# module_4dig7seg.net
KiCad netlist of a schematic drawn in EAGLE
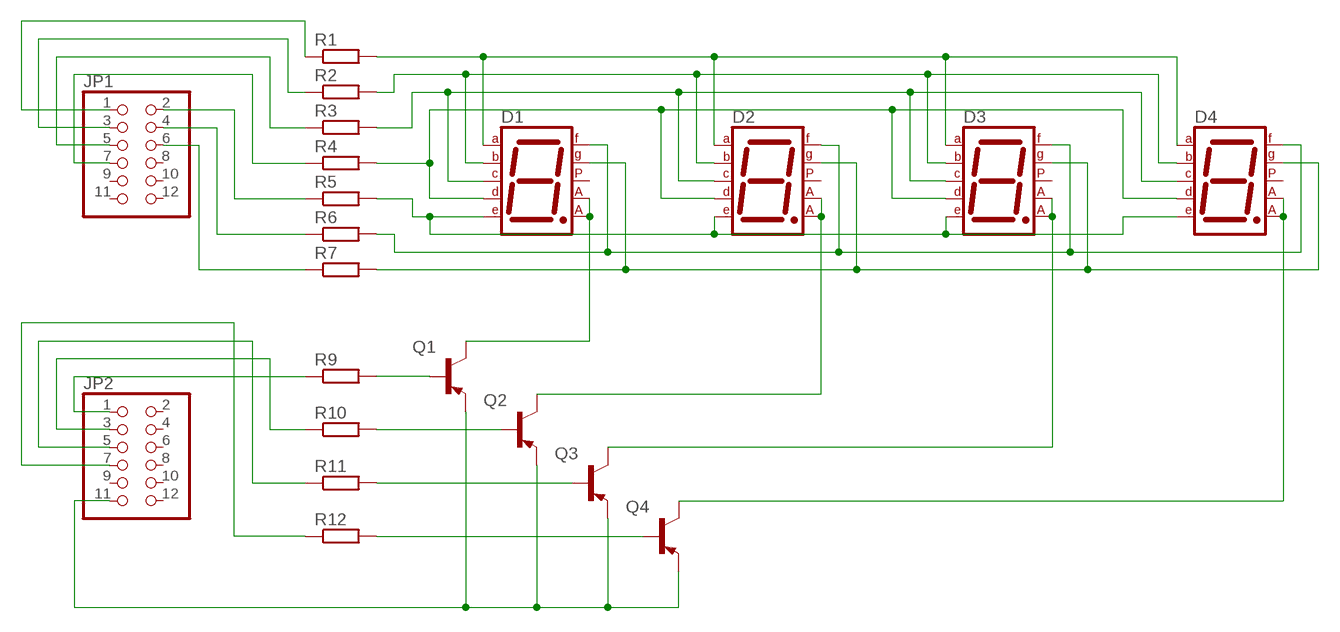
[diagram p0: schematic, sheet 1]

(export (version "E")
  (design (tool "Eeschema 10.0.6"))
  (components
    (comp (ref "D1")
      (value "7SEG-CA")
      (footprint "eagle-import:7SEG-13")
      (libsource (lib "eagle-import") (part "7SEG-CA"))
    )
    (comp (ref "D2")
      (value "7SEG-CA")
      (footprint "eagle-import:7SEG-13")
      (libsource (lib "eagle-import") (part "7SEG-CA"))
    )
    (comp (ref "D3")
      (value "7SEG-CA")
      (footprint "eagle-import:7SEG-13")
      (libsource (lib "eagle-import") (part "7SEG-CA"))
    )
    (comp (ref "D4")
      (value "7SEG-CA")
      (footprint "eagle-import:7SEG-13")
      (libsource (lib "eagle-import") (part "7SEG-CA"))
    )
    (comp (ref "JP1")
      (value "PINHD-2X6/90")
      (footprint "eagle-import:2X06_90")
      (libsource (lib "eagle-import") (part "PINHD-2X6/90"))
    )
    (comp (ref "JP2")
      (value "PINHD-2X6/90")
      (footprint "eagle-import:2X06_90")
      (libsource (lib "eagle-import") (part "PINHD-2X6/90"))
    )
    (comp (ref "Q1")
      (value "2N3906")
      (footprint "eagle-import:TO92")
      (libsource (lib "eagle-import") (part "2N3906"))
    )
    (comp (ref "Q2")
      (value "2N3906")
      (footprint "eagle-import:TO92")
      (libsource (lib "eagle-import") (part "2N3906"))
    )
    (comp (ref "Q3")
      (value "2N3906")
      (footprint "eagle-import:TO92")
      (libsource (lib "eagle-import") (part "2N3906"))
    )
    (comp (ref "Q4")
      (value "2N3906")
      (footprint "eagle-import:TO92")
      (libsource (lib "eagle-import") (part "2N3906"))
    )
    (comp (ref "R1")
      (value "R-EU_0204/7")
      (footprint "eagle-import:0204_7")
      (libsource (lib "eagle-import") (part "R-EU_0204/7"))
    )
    (comp (ref "R2")
      (value "R-EU_0204/7")
      (footprint "eagle-import:0204_7")
      (libsource (lib "eagle-import") (part "R-EU_0204/7"))
    )
    (comp (ref "R3")
      (value "R-EU_0204/7")
      (footprint "eagle-import:0204_7")
      (libsource (lib "eagle-import") (part "R-EU_0204/7"))
    )
    (comp (ref "R4")
      (value "R-EU_0204/7")
      (footprint "eagle-import:0204_7")
      (libsource (lib "eagle-import") (part "R-EU_0204/7"))
    )
    (comp (ref "R5")
      (value "R-EU_0204/7")
      (footprint "eagle-import:0204_7")
      (libsource (lib "eagle-import") (part "R-EU_0204/7"))
    )
    (comp (ref "R6")
      (value "R-EU_0204/7")
      (footprint "eagle-import:0204_7")
      (libsource (lib "eagle-import") (part "R-EU_0204/7"))
    )
    (comp (ref "R7")
      (value "R-EU_0204/7")
      (footprint "eagle-import:0204_7")
      (libsource (lib "eagle-import") (part "R-EU_0204/7"))
    )
    (comp (ref "R9")
      (value "R-EU_0204/7")
      (footprint "eagle-import:0204_7")
      (libsource (lib "eagle-import") (part "R-EU_0204/7"))
    )
    (comp (ref "R10")
      (value "R-EU_0204/7")
      (footprint "eagle-import:0204_7")
      (libsource (lib "eagle-import") (part "R-EU_0204/7"))
    )
    (comp (ref "R11")
      (value "R-EU_0204/7")
      (footprint "eagle-import:0204_7")
      (libsource (lib "eagle-import") (part "R-EU_0204/7"))
    )
    (comp (ref "R12")
      (value "R-EU_0204/7")
      (footprint "eagle-import:0204_7")
      (libsource (lib "eagle-import") (part "R-EU_0204/7"))
    )
  )
  (nets
    (net (code "1") (name "Net-(D1-A)") (class "Default")
      (node (ref "D1") (pin "7") (pinfunction "A_7") (pintype "passive"))
      (node (ref "D2") (pin "7") (pinfunction "A_7") (pintype "passive"))
      (node (ref "D3") (pin "7") (pinfunction "A_7") (pintype "passive"))
      (node (ref "D4") (pin "7") (pinfunction "A_7") (pintype "passive"))
      (node (ref "R1") (pin "2") (pinfunction "2_2") (pintype "passive"))
    )
    (net (code "2") (name "Net-(D1-B)") (class "Default")
      (node (ref "D1") (pin "6") (pinfunction "B_6") (pintype "passive"))
      (node (ref "D2") (pin "6") (pinfunction "B_6") (pintype "passive"))
      (node (ref "D3") (pin "6") (pinfunction "B_6") (pintype "passive"))
      (node (ref "D4") (pin "6") (pinfunction "B_6") (pintype "passive"))
      (node (ref "R2") (pin "2") (pinfunction "2_2") (pintype "passive"))
    )
    (net (code "3") (name "Net-(D1-C)") (class "Default")
      (node (ref "D1") (pin "4") (pinfunction "C_4") (pintype "passive"))
      (node (ref "D2") (pin "4") (pinfunction "C_4") (pintype "passive"))
      (node (ref "D3") (pin "4") (pinfunction "C_4") (pintype "passive"))
      (node (ref "D4") (pin "4") (pinfunction "C_4") (pintype "passive"))
      (node (ref "R3") (pin "2") (pinfunction "2_2") (pintype "passive"))
    )
    (net (code "4") (name "Net-(D1-CA1)") (class "Default")
      (node (ref "D1") (pin "3") (pinfunction "CA1_3") (pintype "passive"))
      (node (ref "D1") (pin "8") (pinfunction "CA2_8") (pintype "passive"))
      (node (ref "Q1") (pin "1") (pinfunction "C_1") (pintype "passive"))
    )
    (net (code "5") (name "Net-(D1-D)") (class "Default")
      (node (ref "D1") (pin "2") (pinfunction "D_2") (pintype "passive"))
      (node (ref "D2") (pin "2") (pinfunction "D_2") (pintype "passive"))
      (node (ref "D3") (pin "2") (pinfunction "D_2") (pintype "passive"))
      (node (ref "D4") (pin "2") (pinfunction "D_2") (pintype "passive"))
      (node (ref "R4") (pin "2") (pinfunction "2_2") (pintype "passive"))
    )
    (net (code "6") (name "Net-(D1-E)") (class "Default")
      (node (ref "D1") (pin "1") (pinfunction "E_1") (pintype "passive"))
      (node (ref "D2") (pin "1") (pinfunction "E_1") (pintype "passive"))
      (node (ref "D3") (pin "1") (pinfunction "E_1") (pintype "passive"))
      (node (ref "D4") (pin "1") (pinfunction "E_1") (pintype "passive"))
      (node (ref "R5") (pin "2") (pinfunction "2_2") (pintype "passive"))
    )
    (net (code "7") (name "Net-(D1-F)") (class "Default")
      (node (ref "D1") (pin "9") (pinfunction "F_9") (pintype "passive"))
      (node (ref "D2") (pin "9") (pinfunction "F_9") (pintype "passive"))
      (node (ref "D3") (pin "9") (pinfunction "F_9") (pintype "passive"))
      (node (ref "D4") (pin "9") (pinfunction "F_9") (pintype "passive"))
      (node (ref "R6") (pin "2") (pinfunction "2_2") (pintype "passive"))
    )
    (net (code "8") (name "Net-(D1-G)") (class "Default")
      (node (ref "D1") (pin "10") (pinfunction "G_10") (pintype "passive"))
      (node (ref "D2") (pin "10") (pinfunction "G_10") (pintype "passive"))
      (node (ref "D3") (pin "10") (pinfunction "G_10") (pintype "passive"))
      (node (ref "D4") (pin "10") (pinfunction "G_10") (pintype "passive"))
      (node (ref "R7") (pin "2") (pinfunction "2_2") (pintype "passive"))
    )
    (net (code "9") (name "Net-(D2-CA1)") (class "Default")
      (node (ref "D2") (pin "3") (pinfunction "CA1_3") (pintype "passive"))
      (node (ref "D2") (pin "8") (pinfunction "CA2_8") (pintype "passive"))
      (node (ref "Q2") (pin "1") (pinfunction "C_1") (pintype "passive"))
    )
    (net (code "10") (name "Net-(D3-CA1)") (class "Default")
      (node (ref "D3") (pin "3") (pinfunction "CA1_3") (pintype "passive"))
      (node (ref "D3") (pin "8") (pinfunction "CA2_8") (pintype "passive"))
      (node (ref "Q3") (pin "1") (pinfunction "C_1") (pintype "passive"))
    )
    (net (code "11") (name "Net-(D4-CA1)") (class "Default")
      (node (ref "D4") (pin "3") (pinfunction "CA1_3") (pintype "passive"))
      (node (ref "D4") (pin "8") (pinfunction "CA2_8") (pintype "passive"))
      (node (ref "Q4") (pin "1") (pinfunction "C_1") (pintype "passive"))
    )
    (net (code "12") (name "Net-(JP1-Pad1)") (class "Default")
      (node (ref "JP1") (pin "1") (pinfunction "1_1") (pintype "passive"))
      (node (ref "R1") (pin "1") (pinfunction "1_1") (pintype "passive"))
    )
    (net (code "13") (name "Net-(JP1-Pad2)") (class "Default")
      (node (ref "JP1") (pin "2") (pinfunction "2_2") (pintype "passive"))
      (node (ref "R5") (pin "1") (pinfunction "1_1") (pintype "passive"))
    )
    (net (code "14") (name "Net-(JP1-Pad3)") (class "Default")
      (node (ref "JP1") (pin "3") (pinfunction "3_3") (pintype "passive"))
      (node (ref "R2") (pin "1") (pinfunction "1_1") (pintype "passive"))
    )
    (net (code "15") (name "Net-(JP1-Pad4)") (class "Default")
      (node (ref "JP1") (pin "4") (pinfunction "4_4") (pintype "passive"))
      (node (ref "R6") (pin "1") (pinfunction "1_1") (pintype "passive"))
    )
    (net (code "16") (name "Net-(JP1-Pad5)") (class "Default")
      (node (ref "JP1") (pin "5") (pinfunction "5_5") (pintype "passive"))
      (node (ref "R3") (pin "1") (pinfunction "1_1") (pintype "passive"))
    )
    (net (code "17") (name "Net-(JP1-Pad6)") (class "Default")
      (node (ref "JP1") (pin "6") (pinfunction "6_6") (pintype "passive"))
      (node (ref "R7") (pin "1") (pinfunction "1_1") (pintype "passive"))
    )
    (net (code "18") (name "Net-(JP1-Pad7)") (class "Default")
      (node (ref "JP1") (pin "7") (pinfunction "7_7") (pintype "passive"))
      (node (ref "R4") (pin "1") (pinfunction "1_1") (pintype "passive"))
    )
    (net (code "19") (name "Net-(JP2-Pad1)") (class "Default")
      (node (ref "JP2") (pin "1") (pinfunction "1_1") (pintype "passive"))
      (node (ref "R9") (pin "1") (pinfunction "1_1") (pintype "passive"))
    )
    (net (code "20") (name "Net-(JP2-Pad3)") (class "Default")
      (node (ref "JP2") (pin "3") (pinfunction "3_3") (pintype "passive"))
      (node (ref "R10") (pin "1") (pinfunction "1_1") (pintype "passive"))
    )
    (net (code "21") (name "Net-(JP2-Pad5)") (class "Default")
      (node (ref "JP2") (pin "5") (pinfunction "5_5") (pintype "passive"))
      (node (ref "R11") (pin "1") (pinfunction "1_1") (pintype "passive"))
    )
    (net (code "22") (name "Net-(JP2-Pad7)") (class "Default")
      (node (ref "JP2") (pin "7") (pinfunction "7_7") (pintype "passive"))
      (node (ref "R12") (pin "1") (pinfunction "1_1") (pintype "passive"))
    )
    (net (code "23") (name "Net-(Q1-B)") (class "Default")
      (node (ref "Q1") (pin "2") (pinfunction "B_2") (pintype "passive"))
      (node (ref "R9") (pin "2") (pinfunction "2_2") (pintype "passive"))
    )
    (net (code "24") (name "Net-(Q1-E)") (class "Default")
      (node (ref "JP2") (pin "11") (pinfunction "11_11") (pintype "passive"))
      (node (ref "Q1") (pin "3") (pinfunction "E_3") (pintype "passive"))
      (node (ref "Q2") (pin "3") (pinfunction "E_3") (pintype "passive"))
      (node (ref "Q3") (pin "3") (pinfunction "E_3") (pintype "passive"))
      (node (ref "Q4") (pin "3") (pinfunction "E_3") (pintype "passive"))
    )
    (net (code "25") (name "Net-(Q2-B)") (class "Default")
      (node (ref "Q2") (pin "2") (pinfunction "B_2") (pintype "passive"))
      (node (ref "R10") (pin "2") (pinfunction "2_2") (pintype "passive"))
    )
    (net (code "26") (name "Net-(Q3-B)") (class "Default")
      (node (ref "Q3") (pin "2") (pinfunction "B_2") (pintype "passive"))
      (node (ref "R11") (pin "2") (pinfunction "2_2") (pintype "passive"))
    )
    (net (code "27") (name "Net-(Q4-B)") (class "Default")
      (node (ref "Q4") (pin "2") (pinfunction "B_2") (pintype "passive"))
      (node (ref "R12") (pin "2") (pinfunction "2_2") (pintype "passive"))
    )
    (net (code "28") (name "unconnected-(D1-DP-Pad5)") (class "Default")
      (node (ref "D1") (pin "5") (pinfunction "DP_5") (pintype "passive"))
    )
    (net (code "29") (name "unconnected-(D2-DP-Pad5)") (class "Default")
      (node (ref "D2") (pin "5") (pinfunction "DP_5") (pintype "passive"))
    )
    (net (code "30") (name "unconnected-(D3-DP-Pad5)") (class "Default")
      (node (ref "D3") (pin "5") (pinfunction "DP_5") (pintype "passive"))
    )
    (net (code "31") (name "unconnected-(D4-DP-Pad5)") (class "Default")
      (node (ref "D4") (pin "5") (pinfunction "DP_5") (pintype "passive"))
    )
    (net (code "32") (name "unconnected-(JP1-Pad8)") (class "Default")
      (node (ref "JP1") (pin "8") (pinfunction "8_8") (pintype "passive"))
    )
    (net (code "33") (name "unconnected-(JP1-Pad9)") (class "Default")
      (node (ref "JP1") (pin "9") (pinfunction "9_9") (pintype "passive"))
    )
    (net (code "34") (name "unconnected-(JP1-Pad10)") (class "Default")
      (node (ref "JP1") (pin "10") (pinfunction "10_10") (pintype "passive"))
    )
    (net (code "35") (name "unconnected-(JP1-Pad11)") (class "Default")
      (node (ref "JP1") (pin "11") (pinfunction "11_11") (pintype "passive"))
    )
    (net (code "36") (name "unconnected-(JP1-Pad12)") (class "Default")
      (node (ref "JP1") (pin "12") (pinfunction "12_12") (pintype "passive"))
    )
    (net (code "37") (name "unconnected-(JP2-Pad2)") (class "Default")
      (node (ref "JP2") (pin "2") (pinfunction "2_2") (pintype "passive"))
    )
    (net (code "38") (name "unconnected-(JP2-Pad4)") (class "Default")
      (node (ref "JP2") (pin "4") (pinfunction "4_4") (pintype "passive"))
    )
    (net (code "39") (name "unconnected-(JP2-Pad6)") (class "Default")
      (node (ref "JP2") (pin "6") (pinfunction "6_6") (pintype "passive"))
    )
    (net (code "40") (name "unconnected-(JP2-Pad8)") (class "Default")
      (node (ref "JP2") (pin "8") (pinfunction "8_8") (pintype "passive"))
    )
    (net (code "41") (name "unconnected-(JP2-Pad9)") (class "Default")
      (node (ref "JP2") (pin "9") (pinfunction "9_9") (pintype "passive"))
    )
    (net (code "42") (name "unconnected-(JP2-Pad10)") (class "Default")
      (node (ref "JP2") (pin "10") (pinfunction "10_10") (pintype "passive"))
    )
    (net (code "43") (name "unconnected-(JP2-Pad12)") (class "Default")
      (node (ref "JP2") (pin "12") (pinfunction "12_12") (pintype "passive"))
    )
  )
)
